# DC_Link_Sensing.net
KiCad netlist of a schematic drawn in Altium Designer
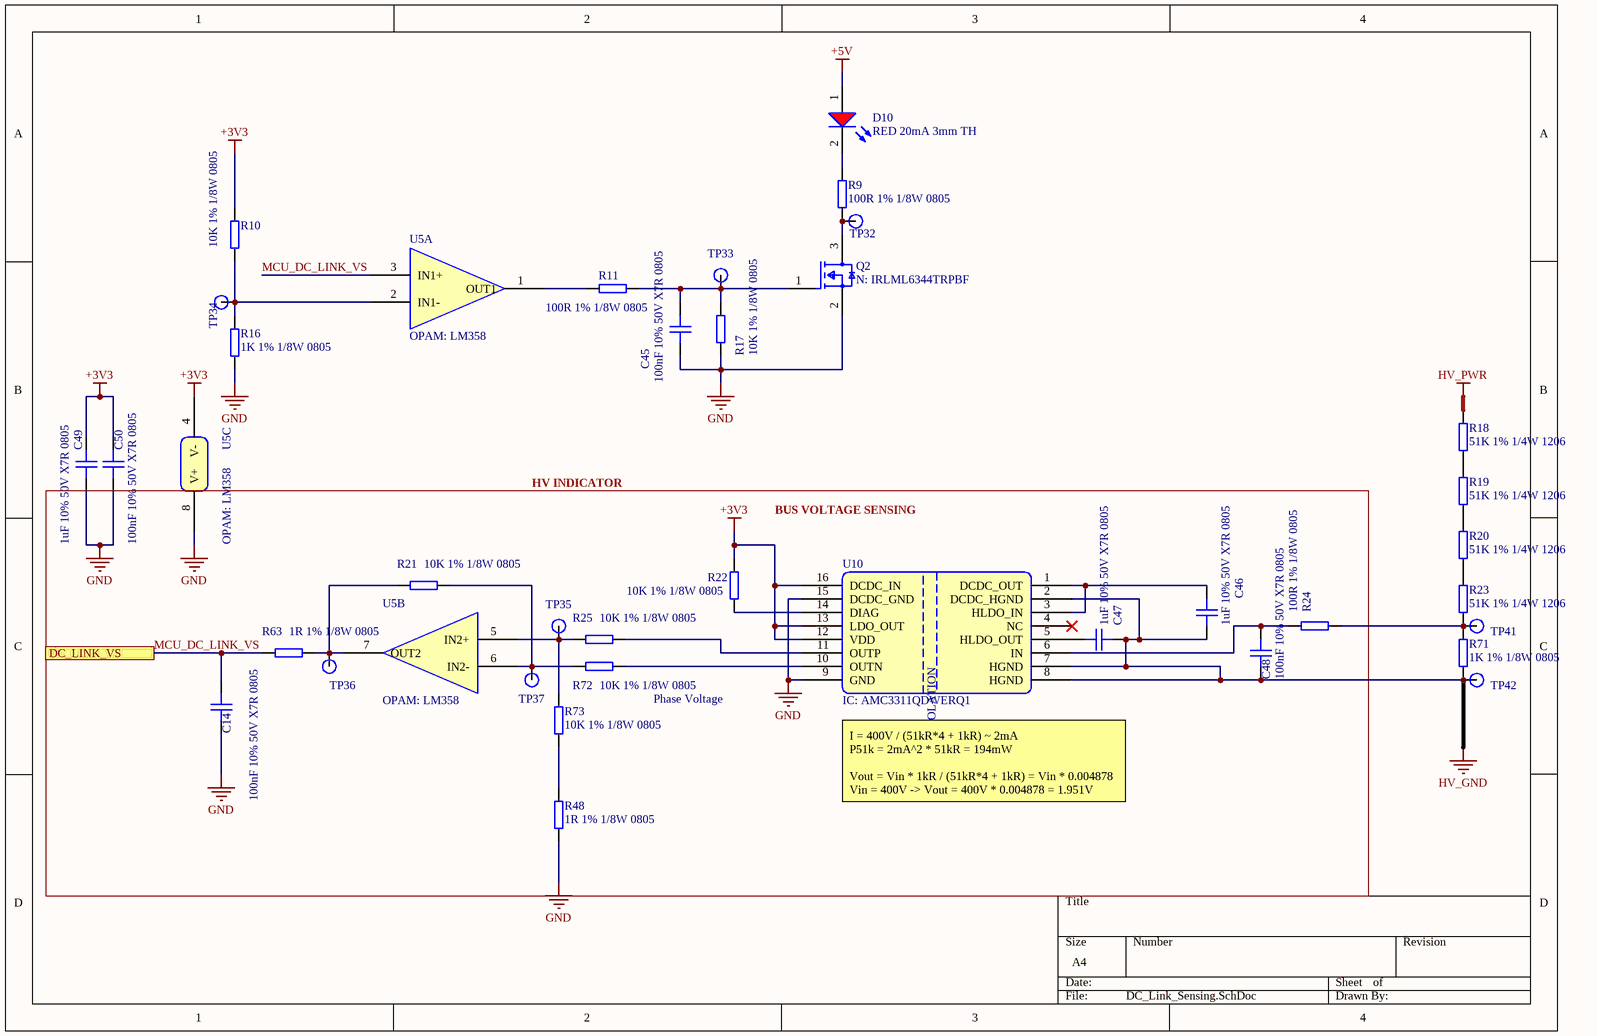
[diagram p0: DC_Link_Sensing.SchDoc]

(export (version "E")
  (design (tool "Eeschema 10.0.6"))
  (components
    (comp (ref "C14")
      (value "100nF 10% 50V X7R 0805")
      (footprint "CAPC2012X10N")
      (description "Multilayer Ceramic Capacitors MLCC - SMD/SMT 50V 0.1uF X7R 0805 10%")
      (fields
        (field (name "MANUFACTURER") "Stackpole Electronics")
        (field (name "MANUFACTURER PART NUMBER") "CML0805X7R104KT50V")
      )
      (libsource (lib "EMEA- E-Tech Racing- I'Escola d'Enginyeria de Barcelona Est") (part "100nF 10% 50V X7R 0805-Symbol-1"))
    )
    (comp (ref "C45")
      (value "100nF 10% 50V X7R 0805")
      (footprint "CAPC2012X10N")
      (description "Multilayer Ceramic Capacitors MLCC - SMD/SMT 50V 0.1uF X7R 0805 10%")
      (fields
        (field (name "MANUFACTURER") "Stackpole Electronics")
        (field (name "MANUFACTURER PART NUMBER") "CML0805X7R104KT50V")
      )
      (libsource (lib "EMEA- E-Tech Racing- I'Escola d'Enginyeria de Barcelona Est") (part "100nF 10% 50V X7R 0805-Symbol-1"))
    )
    (comp (ref "C46")
      (value "1uF 10% 50V X7R 0805")
      (footprint "CAPC2012X10N")
      (fields
        (field (name "MANUFACTURER PART NUMBER") "C2012X7R1H105K125AB")
        (field (name "MANUFACTURER") "TDK")
      )
      (libsource (lib "EMEA- E-Tech Racing- I'Escola d'Enginyeria de Barcelona Est") (part "68pF 10 630V C0G 0805"))
    )
    (comp (ref "C47")
      (value "1uF 10% 50V X7R 0805")
      (footprint "CAPC2012X10N")
      (fields
        (field (name "MANUFACTURER PART NUMBER") "C2012X7R1H105K125AB")
        (field (name "MANUFACTURER") "TDK")
      )
      (libsource (lib "EMEA- E-Tech Racing- I'Escola d'Enginyeria de Barcelona Est") (part "68pF 10 630V C0G 0805"))
    )
    (comp (ref "C48")
      (value "100nF 10% 50V X7R 0805")
      (footprint "CAPC2012X10N")
      (description "Multilayer Ceramic Capacitors MLCC - SMD/SMT 50V 0.1uF X7R 0805 10%")
      (fields
        (field (name "MANUFACTURER") "Stackpole Electronics")
        (field (name "MANUFACTURER PART NUMBER") "CML0805X7R104KT50V")
      )
      (libsource (lib "EMEA- E-Tech Racing- I'Escola d'Enginyeria de Barcelona Est") (part "100nF 10% 50V X7R 0805-Symbol-1"))
    )
    (comp (ref "C49")
      (value "1uF 10% 50V X7R 0805")
      (footprint "CAPC2012X10N")
      (fields
        (field (name "MANUFACTURER PART NUMBER") "C2012X7R1H105K125AB")
        (field (name "MANUFACTURER") "TDK")
      )
      (libsource (lib "EMEA- E-Tech Racing- I'Escola d'Enginyeria de Barcelona Est") (part "68pF 10 630V C0G 0805"))
    )
    (comp (ref "C50")
      (value "100nF 10% 50V X7R 0805")
      (footprint "CAPC2012X10N")
      (description "Multilayer Ceramic Capacitors MLCC - SMD/SMT 50V 0.1uF X7R 0805 10%")
      (fields
        (field (name "MANUFACTURER") "Stackpole Electronics")
        (field (name "MANUFACTURER PART NUMBER") "CML0805X7R104KT50V")
      )
      (libsource (lib "EMEA- E-Tech Racing- I'Escola d'Enginyeria de Barcelona Est") (part "100nF 10% 50V X7R 0805-Symbol-1"))
    )
    (comp (ref "D10")
      (value "RED 20mA 3mm TH")
      (footprint "WL-TMRC_D3.95H5.3")
      (description "LED RED DIFFUSED 3MM ROUND T/H")
      (fields
        (field (name "MANUFACTURER") "Wurth Elektronik")
        (field (name "MANUFACTURER PART NUMBER") "151031SS06000")
      )
      (libsource (lib "EMEA- E-Tech Racing- I'Escola d'Enginyeria de Barcelona Est") (part "LED_Red_1A-2K"))
    )
    (comp (ref "Q2")
      (value "N: IRLML6344TRPBF")
      (footprint "FP-SOT23-MFG")
      (description "N-Channel 30 V 5A (Ta) 1.3W (Ta) Surface Mount Micro3™/SOT-23")
      (fields
        (field (name "MANUFACTURER PART NUMBER") "IRLML6344TRPBF")
        (field (name "MANUFACTURER") "Infineon")
      )
      (libsource (lib "EMEA- E-Tech Racing- I'Escola d'Enginyeria de Barcelona Est") (part "N{colon} IRLML6344TRPBF-Symbol-1"))
    )
    (comp (ref "R9")
      (value "100R 1% 1/8W 0805")
      (footprint "RESC2012X05N")
      (description "Res Thick Film 0805 100 Ohm 1% 0.125W ±100ppm/°C Molded SMD Paper T/R")
      (fields (field (name "TOLERANCE") "1%") (field (name "MANUFACTURER PART NUMBER") "RMCF0805FT100R"))
      (libsource (lib "EMEA- E-Tech Racing- I'Escola d'Enginyeria de Barcelona Est") (part "100R 1 1/8W 0805"))
    )
    (comp (ref "R10")
      (value "10K 1% 1/8W 0805")
      (footprint "RESC2012X05N")
      (description "Res Thick Film 0805 10K Ohm 1% 0.125W ±100ppm/°C Molded SMD Paper T/R")
      (fields
        (field (name "MANUFACTURER") "Stackpole Electronics")
        (field (name "MANUFACTURER PART NUMBER") "RMCF0805FT10K0")
      )
      (libsource (lib "EMEA- E-Tech Racing- I'Escola d'Enginyeria de Barcelona Est") (part "100R 1 1/8W 0805"))
    )
    (comp (ref "R11")
      (value "100R 1% 1/8W 0805")
      (footprint "RESC2012X05N")
      (description "Res Thick Film 0805 100 Ohm 1% 0.125W ±100ppm/°C Molded SMD Paper T/R")
      (fields (field (name "TOLERANCE") "1%") (field (name "MANUFACTURER PART NUMBER") "RMCF0805FT100R"))
      (libsource (lib "EMEA- E-Tech Racing- I'Escola d'Enginyeria de Barcelona Est") (part "100R 1 1/8W 0805"))
    )
    (comp (ref "R16")
      (value "1K 1% 1/8W 0805")
      (footprint "RESC2012X05N")
      (description "Res Thick Film 0805 1K Ohm 1% 0.125W ±100ppm/°C Molded SMD Paper T/R")
      (fields (field (name "TOLERANCE") "1%") (field (name "MANUFACTURER") "Stackpole Electronics"))
      (libsource (lib "EMEA- E-Tech Racing- I'Escola d'Enginyeria de Barcelona Est") (part "100R 1 1/8W 0805"))
    )
    (comp (ref "R17")
      (value "10K 1% 1/8W 0805")
      (footprint "RESC2012X05N")
      (description "Res Thick Film 0805 10K Ohm 1% 0.125W ±100ppm/°C Molded SMD Paper T/R")
      (fields (field (name "TOLERANCE") "1%") (field (name "MANUFACTURER PART NUMBER") "RMCF0805FT10K0"))
      (libsource (lib "EMEA- E-Tech Racing- I'Escola d'Enginyeria de Barcelona Est") (part "100R 1 1/8W 0805"))
    )
    (comp (ref "R18")
      (value "51K 1% 1/4W 1206")
      (footprint "RESC3116X06N")
      (description "Res Thick Film 1206 51K Ohm 1% 0.25W(1/4W) ±100ppm/C Pad SMD T/R Automotive AEC-Q200")
      (fields (field (name "MANUFACTURER") "Stackpole Electronics") (field (name "TOLERANCE") "5%"))
      (libsource (lib "EMEA- E-Tech Racing- I'Escola d'Enginyeria de Barcelona Est") (part "100R 1 1/8W 0805"))
    )
    (comp (ref "R19")
      (value "51K 1% 1/4W 1206")
      (footprint "RESC3116X06N")
      (description "Res Thick Film 1206 51K Ohm 1% 0.25W(1/4W) ±100ppm/C Pad SMD T/R Automotive AEC-Q200")
      (fields (field (name "MANUFACTURER") "Stackpole Electronics") (field (name "TOLERANCE") "5%"))
      (libsource (lib "EMEA- E-Tech Racing- I'Escola d'Enginyeria de Barcelona Est") (part "100R 1 1/8W 0805"))
    )
    (comp (ref "R20")
      (value "51K 1% 1/4W 1206")
      (footprint "RESC3116X06N")
      (description "Res Thick Film 1206 51K Ohm 1% 0.25W(1/4W) ±100ppm/C Pad SMD T/R Automotive AEC-Q200")
      (fields (field (name "MANUFACTURER") "Stackpole Electronics") (field (name "TOLERANCE") "5%"))
      (libsource (lib "EMEA- E-Tech Racing- I'Escola d'Enginyeria de Barcelona Est") (part "100R 1 1/8W 0805"))
    )
    (comp (ref "R21")
      (value "10K 1% 1/8W 0805")
      (footprint "RESC2012X05N")
      (description "Res Thick Film 0805 10K Ohm 1% 0.125W ±100ppm/°C Molded SMD Paper T/R")
      (fields
        (field (name "MANUFACTURER") "Stackpole Electronics")
        (field (name "MANUFACTURER PART NUMBER") "RMCF0805FT10K0")
      )
      (libsource (lib "EMEA- E-Tech Racing- I'Escola d'Enginyeria de Barcelona Est") (part "100R 1 1/8W 0805"))
    )
    (comp (ref "R22")
      (value "10K 1% 1/8W 0805")
      (footprint "RESC2012X05N")
      (description "Res Thick Film 0805 10K Ohm 1% 0.125W ±100ppm/°C Molded SMD Paper T/R")
      (fields
        (field (name "MANUFACTURER") "Stackpole Electronics")
        (field (name "MANUFACTURER PART NUMBER") "RMCF0805FT10K0")
      )
      (libsource (lib "EMEA- E-Tech Racing- I'Escola d'Enginyeria de Barcelona Est") (part "100R 1 1/8W 0805"))
    )
    (comp (ref "R23")
      (value "51K 1% 1/4W 1206")
      (footprint "RESC3116X06N")
      (description "Res Thick Film 1206 51K Ohm 1% 0.25W(1/4W) ±100ppm/C Pad SMD T/R Automotive AEC-Q200")
      (fields (field (name "MANUFACTURER") "Stackpole Electronics") (field (name "TOLERANCE") "5%"))
      (libsource (lib "EMEA- E-Tech Racing- I'Escola d'Enginyeria de Barcelona Est") (part "100R 1 1/8W 0805"))
    )
    (comp (ref "R24")
      (value "100R 1% 1/8W 0805")
      (footprint "RESC2012X05N")
      (description "Res Thick Film 0805 100 Ohm 1% 0.125W ±100ppm/°C Molded SMD Paper T/R")
      (fields (field (name "TOLERANCE") "1%") (field (name "MANUFACTURER PART NUMBER") "RMCF0805FT100R"))
      (libsource (lib "EMEA- E-Tech Racing- I'Escola d'Enginyeria de Barcelona Est") (part "100R 1 1/8W 0805"))
    )
    (comp (ref "R25")
      (value "10K 1% 1/8W 0805")
      (footprint "RESC2012X05N")
      (description "Res Thick Film 0805 10K Ohm 1% 0.125W ±100ppm/°C Molded SMD Paper T/R")
      (fields
        (field (name "MANUFACTURER") "Stackpole Electronics")
        (field (name "MANUFACTURER PART NUMBER") "RMCF0805FT10K0")
      )
      (libsource (lib "EMEA- E-Tech Racing- I'Escola d'Enginyeria de Barcelona Est") (part "100R 1 1/8W 0805"))
    )
    (comp (ref "R48")
      (value "1R 1% 1/8W 0805")
      (footprint "RESC2012X05N")
      (description "Res Thick Film 0805 1 Ohm 1% 0.125W ±100ppm/°C Molded SMD Paper T/R")
      (fields
        (field (name "MANUFACTURER PART NUMBER") "RMCF0805FT1R00")
        (field (name "MANUFACTURER") "Stackpole Electronics")
      )
      (libsource (lib "EMEA- E-Tech Racing- I'Escola d'Enginyeria de Barcelona Est") (part "100R 1 1/8W 0805"))
    )
    (comp (ref "R63")
      (value "1R 1% 1/8W 0805")
      (footprint "RESC2012X05N")
      (description "Res Thick Film 0805 1 Ohm 1% 0.125W ±100ppm/°C Molded SMD Paper T/R")
      (fields
        (field (name "MANUFACTURER PART NUMBER") "RMCF0805FT1R00")
        (field (name "MANUFACTURER") "Stackpole Electronics")
      )
      (libsource (lib "EMEA- E-Tech Racing- I'Escola d'Enginyeria de Barcelona Est") (part "100R 1 1/8W 0805"))
    )
    (comp (ref "R71")
      (value "1K 1% 1/8W 0805")
      (footprint "RESC2012X05N")
      (description "Res Thick Film 0805 1K Ohm 1% 0.125W ±100ppm/°C Molded SMD Paper T/R")
      (fields (field (name "TOLERANCE") "1%") (field (name "MANUFACTURER") "Stackpole Electronics"))
      (libsource (lib "EMEA- E-Tech Racing- I'Escola d'Enginyeria de Barcelona Est") (part "100R 1 1/8W 0805"))
    )
    (comp (ref "R72")
      (value "10K 1% 1/8W 0805")
      (footprint "RESC2012X05N")
      (description "Res Thick Film 0805 10K Ohm 1% 0.125W ±100ppm/°C Molded SMD Paper T/R")
      (fields
        (field (name "MANUFACTURER") "Stackpole Electronics")
        (field (name "MANUFACTURER PART NUMBER") "RMCF0805FT10K0")
      )
      (libsource (lib "EMEA- E-Tech Racing- I'Escola d'Enginyeria de Barcelona Est") (part "100R 1 1/8W 0805"))
    )
    (comp (ref "R73")
      (value "10K 1% 1/8W 0805")
      (footprint "RESC2012X05N")
      (description "Res Thick Film 0805 10K Ohm 1% 0.125W ±100ppm/°C Molded SMD Paper T/R")
      (fields
        (field (name "MANUFACTURER") "Stackpole Electronics")
        (field (name "MANUFACTURER PART NUMBER") "RMCF0805FT10K0")
      )
      (libsource (lib "EMEA- E-Tech Racing- I'Escola d'Enginyeria de Barcelona Est") (part "100R 1 1/8W 0805"))
    )
    (comp (ref "TP32")
      (value "TestPoint")
      (footprint "Test Point-Footprint-1")
      (libsource (lib "EMEA- E-Tech Racing- I'Escola d'Enginyeria de Barcelona Est") (part "New symbol 1"))
    )
    (comp (ref "TP33")
      (value "TestPoint")
      (footprint "Test Point-Footprint-1")
      (libsource (lib "EMEA- E-Tech Racing- I'Escola d'Enginyeria de Barcelona Est") (part "New symbol 1"))
    )
    (comp (ref "TP34")
      (value "TestPoint")
      (footprint "Test Point-Footprint-1")
      (libsource (lib "EMEA- E-Tech Racing- I'Escola d'Enginyeria de Barcelona Est") (part "New symbol 1"))
    )
    (comp (ref "TP35")
      (value "TestPoint")
      (footprint "Test Point-Footprint-1")
      (libsource (lib "EMEA- E-Tech Racing- I'Escola d'Enginyeria de Barcelona Est") (part "New symbol 1"))
    )
    (comp (ref "TP36")
      (value "TestPoint")
      (footprint "Test Point-Footprint-1")
      (libsource (lib "EMEA- E-Tech Racing- I'Escola d'Enginyeria de Barcelona Est") (part "New symbol 1"))
    )
    (comp (ref "TP37")
      (value "TestPoint")
      (footprint "Test Point-Footprint-1")
      (libsource (lib "EMEA- E-Tech Racing- I'Escola d'Enginyeria de Barcelona Est") (part "New symbol 1"))
    )
    (comp (ref "TP41")
      (value "TestPoint")
      (footprint "Test Point-Footprint-1")
      (libsource (lib "EMEA- E-Tech Racing- I'Escola d'Enginyeria de Barcelona Est") (part "New symbol 1"))
    )
    (comp (ref "TP42")
      (value "TestPoint")
      (footprint "Test Point-Footprint-1")
      (libsource (lib "EMEA- E-Tech Racing- I'Escola d'Enginyeria de Barcelona Est") (part "New symbol 1"))
    )
    (comp (ref "U5")
      (value "OPAM: LM358")
      (footprint "FP-D0008A-IPC_C")
      (description "Dual, 30-V, 700-kHz, 3-mV offset voltage operational amplifier 8-SOIC 0 to 70")
      (fields
        (field (name "MANUFACTURER") "Texas Instruments")
        (field (name "MANUFACTURER PART NUMBER") "LM358BAIDR")
      )
      (libsource (lib "EMEA- E-Tech Racing- I'Escola d'Enginyeria de Barcelona Est") (part "OP{colon} LM358"))
    )
    (comp (ref "U10")
      (value "IC: AMC3311QDWERQ1")
      (footprint "SOIC127P1030X265-16N")
      (fields
        (field (name "MANUFACTURER") "Texas Instruments")
        (field (name "MANUFACTURER PART NUMBER") "AMC3311QDWERQ1")
      )
      (libsource (lib "EMEA- E-Tech Racing- I'Escola d'Enginyeria de Barcelona Est") (part "AMC3311"))
    )
  )
  (nets
    (net (code "1") (name "+3V3") (class "Default")
      (node (ref "C49") (pin "2") (pinfunction "2_2") (pintype "passive"))
      (node (ref "C50") (pin "2") (pinfunction "2_2") (pintype "passive"))
      (node (ref "R10") (pin "2") (pinfunction "2_2") (pintype "passive"))
      (node (ref "R22") (pin "1") (pinfunction "1_1") (pintype "passive"))
      (node (ref "U10") (pin "12") (pinfunction "VDD_12") (pintype "passive"))
      (node (ref "U10") (pin "13") (pinfunction "LDO_OUT_13") (pintype "passive"))
      (node (ref "U10") (pin "16") (pinfunction "DCDC_IN_16") (pintype "passive"))
      (node (ref "U5") (pin "4") (pinfunction "V-_4") (pintype "passive"))
    )
    (net (code "2") (name "+5V") (class "Default")
      (node (ref "D10") (pin "1") (pinfunction "A_1") (pintype "passive"))
    )
    (net (code "3") (name "/MCU_DC_LINK_VS") (class "Default")
      (node (ref "C14") (pin "2") (pinfunction "2_2") (pintype "passive"))
      (node (ref "R63") (pin "1") (pinfunction "1_1") (pintype "passive"))
      (node (ref "U5") (pin "3") (pinfunction "IN1+_3") (pintype "passive"))
    )
    (net (code "4") (name "GND") (class "Default")
      (node (ref "C14") (pin "1") (pinfunction "1_1") (pintype "passive"))
      (node (ref "C45") (pin "1") (pinfunction "1_1") (pintype "passive"))
      (node (ref "C49") (pin "1") (pinfunction "1_1") (pintype "passive"))
      (node (ref "C50") (pin "1") (pinfunction "1_1") (pintype "passive"))
      (node (ref "Q2") (pin "2") (pinfunction "S_2") (pintype "passive"))
      (node (ref "R16") (pin "1") (pinfunction "1_1") (pintype "passive"))
      (node (ref "R17") (pin "1") (pinfunction "1_1") (pintype "passive"))
      (node (ref "R48") (pin "1") (pinfunction "1_1") (pintype "passive"))
      (node (ref "U10") (pin "15") (pinfunction "DCDC_GND_15") (pintype "passive"))
      (node (ref "U10") (pin "9") (pinfunction "GND_9") (pintype "passive"))
      (node (ref "U5") (pin "8") (pinfunction "V+_8") (pintype "passive"))
    )
    (net (code "5") (name "HV_GND") (class "Default")
      (node (ref "C46") (pin "1") (pinfunction "1_1") (pintype "passive"))
      (node (ref "C47") (pin "1") (pinfunction "1_1") (pintype "passive"))
      (node (ref "C48") (pin "1") (pinfunction "1_1") (pintype "passive"))
      (node (ref "R71") (pin "1") (pinfunction "1_1") (pintype "passive"))
      (node (ref "TP42") (pin "1") (pinfunction "1_1") (pintype "passive"))
      (node (ref "U10") (pin "2") (pinfunction "DCDC_HGND_2") (pintype "passive"))
      (node (ref "U10") (pin "7") (pinfunction "HGND_7") (pintype "passive"))
      (node (ref "U10") (pin "8") (pinfunction "HGND_8") (pintype "passive"))
    )
    (net (code "6") (name "HV_PWR") (class "Default")
      (node (ref "R18") (pin "2") (pinfunction "2_2") (pintype "passive"))
    )
    (net (code "7") (name "Net-(D10-K)") (class "Default")
      (node (ref "D10") (pin "2") (pinfunction "K_2") (pintype "passive"))
      (node (ref "R9") (pin "2") (pinfunction "2_2") (pintype "passive"))
    )
    (net (code "8") (name "Net-(Q2-D)") (class "Default")
      (node (ref "Q2") (pin "3") (pinfunction "D_3") (pintype "passive"))
      (node (ref "R9") (pin "1") (pinfunction "1_1") (pintype "passive"))
      (node (ref "TP32") (pin "1") (pinfunction "1_1") (pintype "passive"))
    )
    (net (code "9") (name "Net-(Q2-G)") (class "Default")
      (node (ref "C45") (pin "2") (pinfunction "2_2") (pintype "passive"))
      (node (ref "Q2") (pin "1") (pinfunction "G_1") (pintype "passive"))
      (node (ref "R11") (pin "2") (pinfunction "2_2") (pintype "passive"))
      (node (ref "R17") (pin "2") (pinfunction "2_2") (pintype "passive"))
      (node (ref "TP33") (pin "1") (pinfunction "1_1") (pintype "passive"))
    )
    (net (code "10") (name "Net-(R18-Pad1)") (class "Default")
      (node (ref "R18") (pin "1") (pinfunction "1_1") (pintype "passive"))
      (node (ref "R19") (pin "2") (pinfunction "2_2") (pintype "passive"))
    )
    (net (code "11") (name "Net-(R19-Pad1)") (class "Default")
      (node (ref "R19") (pin "1") (pinfunction "1_1") (pintype "passive"))
      (node (ref "R20") (pin "2") (pinfunction "2_2") (pintype "passive"))
    )
    (net (code "12") (name "Net-(R20-Pad1)") (class "Default")
      (node (ref "R20") (pin "1") (pinfunction "1_1") (pintype "passive"))
      (node (ref "R23") (pin "2") (pinfunction "2_2") (pintype "passive"))
    )
    (net (code "13") (name "Net-(R23-Pad1)") (class "Default")
      (node (ref "R23") (pin "1") (pinfunction "1_1") (pintype "passive"))
      (node (ref "R24") (pin "1") (pinfunction "1_1") (pintype "passive"))
      (node (ref "R71") (pin "2") (pinfunction "2_2") (pintype "passive"))
      (node (ref "TP41") (pin "1") (pinfunction "1_1") (pintype "passive"))
    )
    (net (code "14") (name "Net-(R48-Pad2)") (class "Default")
      (node (ref "R48") (pin "2") (pinfunction "2_2") (pintype "passive"))
      (node (ref "R73") (pin "1") (pinfunction "1_1") (pintype "passive"))
    )
    (net (code "15") (name "Net-(U5A-IN1-)") (class "Default")
      (node (ref "R10") (pin "1") (pinfunction "1_1") (pintype "passive"))
      (node (ref "R16") (pin "2") (pinfunction "2_2") (pintype "passive"))
      (node (ref "TP34") (pin "1") (pinfunction "1_1") (pintype "passive"))
      (node (ref "U5") (pin "2") (pinfunction "IN1-_2") (pintype "passive"))
    )
    (net (code "16") (name "Net-(U5A-OUT1)") (class "Default")
      (node (ref "R11") (pin "1") (pinfunction "1_1") (pintype "passive"))
      (node (ref "U5") (pin "1") (pinfunction "OUT1_1") (pintype "passive"))
    )
    (net (code "17") (name "Net-(U5B-IN2+)") (class "Default")
      (node (ref "R25") (pin "1") (pinfunction "1_1") (pintype "passive"))
      (node (ref "R73") (pin "2") (pinfunction "2_2") (pintype "passive"))
      (node (ref "TP35") (pin "1") (pinfunction "1_1") (pintype "passive"))
      (node (ref "U5") (pin "5") (pinfunction "IN2+_5") (pintype "passive"))
    )
    (net (code "18") (name "Net-(U5B-IN2-)") (class "Default")
      (node (ref "R21") (pin "2") (pinfunction "2_2") (pintype "passive"))
      (node (ref "R72") (pin "1") (pinfunction "1_1") (pintype "passive"))
      (node (ref "TP37") (pin "1") (pinfunction "1_1") (pintype "passive"))
      (node (ref "U5") (pin "6") (pinfunction "IN2-_6") (pintype "passive"))
    )
    (net (code "19") (name "Net-(U5B-OUT2)") (class "Default")
      (node (ref "R21") (pin "1") (pinfunction "1_1") (pintype "passive"))
      (node (ref "R63") (pin "2") (pinfunction "2_2") (pintype "passive"))
      (node (ref "TP36") (pin "1") (pinfunction "1_1") (pintype "passive"))
      (node (ref "U5") (pin "7") (pinfunction "OUT2_7") (pintype "passive"))
    )
    (net (code "20") (name "Net-(U10-DCDC_OUT)") (class "Default")
      (node (ref "C46") (pin "2") (pinfunction "2_2") (pintype "passive"))
      (node (ref "U10") (pin "1") (pinfunction "DCDC_OUT_1") (pintype "passive"))
      (node (ref "U10") (pin "3") (pinfunction "HLDO_IN_3") (pintype "passive"))
    )
    (net (code "21") (name "Net-(U10-DIAG)") (class "Default")
      (node (ref "R22") (pin "2") (pinfunction "2_2") (pintype "passive"))
      (node (ref "U10") (pin "14") (pinfunction "DIAG_14") (pintype "passive"))
    )
    (net (code "22") (name "Net-(U10-HLDO_OUT)") (class "Default")
      (node (ref "C47") (pin "2") (pinfunction "2_2") (pintype "passive"))
      (node (ref "U10") (pin "5") (pinfunction "HLDO_OUT_5") (pintype "passive"))
    )
    (net (code "23") (name "Net-(U10-IN)") (class "Default")
      (node (ref "C48") (pin "2") (pinfunction "2_2") (pintype "passive"))
      (node (ref "R24") (pin "2") (pinfunction "2_2") (pintype "passive"))
      (node (ref "U10") (pin "6") (pinfunction "IN_6") (pintype "passive"))
    )
    (net (code "24") (name "Net-(U10-OUTN)") (class "Default")
      (node (ref "R72") (pin "2") (pinfunction "2_2") (pintype "passive"))
      (node (ref "U10") (pin "10") (pinfunction "OUTN_10") (pintype "passive"))
    )
    (net (code "25") (name "Net-(U10-OUTP)") (class "Default")
      (node (ref "R25") (pin "2") (pinfunction "2_2") (pintype "passive"))
      (node (ref "U10") (pin "11") (pinfunction "OUTP_11") (pintype "passive"))
    )
    (net (code "26") (name "unconnected-(U10-NC-Pad4)") (class "Default")
      (node (ref "U10") (pin "4") (pinfunction "NC_4") (pintype "passive+no_connect"))
    )
  )
)
